# MCU.net
KiCad netlist of a schematic drawn in Altium Designer
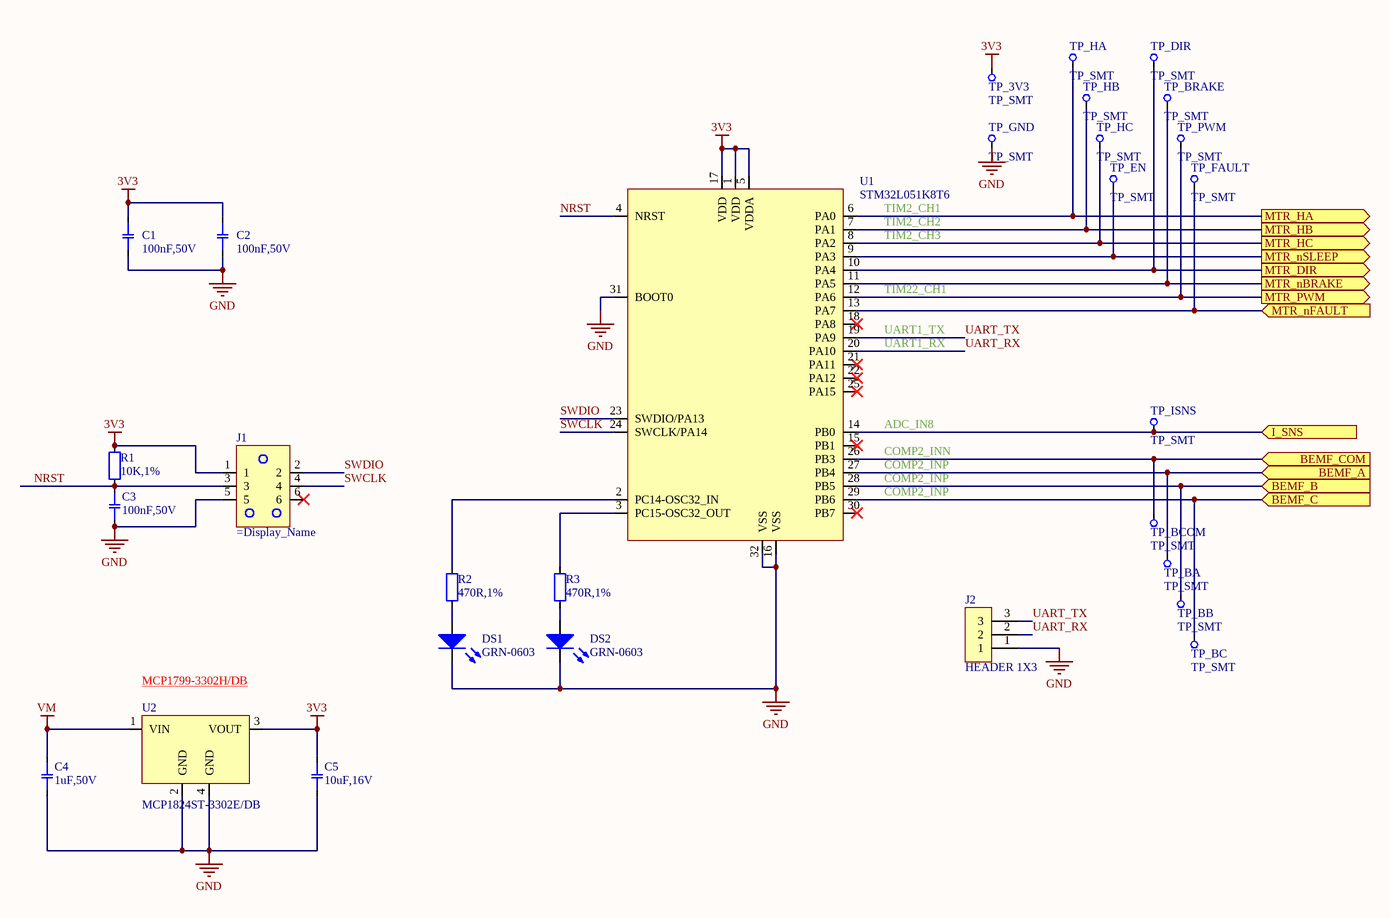
[diagram p0: MCU.SchDoc]

(export (version "E")
  (design (tool "Eeschema 10.0.6"))
  (components
    (comp (ref "C1")
      (value "100nF,50V")
      (footprint "CAPC1608X09N_0603")
      (description "CAP CER 0.1UF 50V 10% X7R 0603")
      (fields (field (name "MANUFACTURER") "Kemet") (field (name "TOLERANCE") "10%"))
      (libsource (lib "library") (part "CAP-NP_1"))
    )
    (comp (ref "C2")
      (value "100nF,50V")
      (footprint "CAPC1608X09N_0603")
      (description "CAP CER 0.1UF 50V 10% X7R 0603")
      (fields (field (name "MANUFACTURER") "Kemet") (field (name "TOLERANCE") "10%"))
      (libsource (lib "library") (part "CAP-NP_1"))
    )
    (comp (ref "C3")
      (value "100nF,50V")
      (footprint "CAPC1608X09N_0603")
      (description "CAP CER 0.1UF 50V 10% X7R 0603")
      (fields (field (name "MANUFACTURER") "Kemet") (field (name "TOLERANCE") "10%"))
      (libsource (lib "library") (part "CAP-NP_1"))
    )
    (comp (ref "C4")
      (value "1uF,50V")
      (footprint "CAPC1608X09N_0603")
      (description "AUTOMOTIVE CAP CER 1UF 50V 10% X5R 0603")
      (fields (field (name "MANUFACTURER") "TDK Corporation") (field (name "TOLERANCE") "10%"))
      (libsource (lib "library") (part "CAP-NP_1"))
    )
    (comp (ref "C5")
      (value "10uF,16V")
      (footprint "CAPC2012X12N_0805")
      (description "CAP CER 10µF ±10% 16V X7R 0805")
      (fields
        (field (name "MANUFACTURER") "Samsung Electro-Mechanics America, Inc.")
        (field (name "TOLERANCE") "10%")
      )
      (libsource (lib "library") (part "CAP-NP_1"))
    )
    (comp (ref "DS1")
      (value "GRN-0603")
      (footprint "LED_SML-LX0603")
      (description "LED GREEN CLEAR 0603 SMD")
      (fields
        (field (name "MANUFACTURER") "Dialight")
        (field (name "MANUFACTURER PART NUMBER") "5988081107F")
      )
      (libsource (lib "library") (part "LED_1"))
    )
    (comp (ref "DS2")
      (value "GRN-0603")
      (footprint "LED_SML-LX0603")
      (description "LED GREEN CLEAR 0603 SMD")
      (fields
        (field (name "MANUFACTURER") "Dialight")
        (field (name "MANUFACTURER PART NUMBER") "5988081107F")
      )
      (libsource (lib "library") (part "LED_1"))
    )
    (comp (ref "J1")
      (value "~")
      (footprint "TAG-CONNECT_TC2030-IDC")
      (description "Tag connect 6 way")
      (libsource (lib "library") (part "TAG-CONNECT_TC2030-IDC"))
    )
    (comp (ref "J2")
      (value "HEADER 1X3")
      (footprint "HIROSE_A2-3PA-2.54DSA")
      (description "CONN 3-pin 2.54mm pitch TH single row")
      (fields
        (field (name "MANUFACTURER") "Hirose")
        (field (name "MANUFACTURER PART NUMBER") "A2-3PA-2.54DSA")
      )
      (libsource (lib "library") (part "HIROSE_A2-3PA-2.54DSA"))
    )
    (comp (ref "R1")
      (value "10K,1%")
      (footprint "RESC1608X06N_0603")
      (description "RES 10.0K OHM 1/10W 1% 0603 SMD")
      (fields (field (name "MANUFACTURER") "Yageo") (field (name "POWER") "0.1W"))
      (libsource (lib "library") (part "RESISTOR_1"))
    )
    (comp (ref "R2")
      (value "470R,1%")
      (footprint "RESC1608X06N_0603")
      (description "RES 470 OHM 1/10W 1% 0603 SMD")
      (fields (field (name "MANUFACTURER") "Rohm Semiconductor") (field (name "POWER") "0.1W"))
      (libsource (lib "library") (part "RESISTOR_1"))
    )
    (comp (ref "R3")
      (value "470R,1%")
      (footprint "RESC1608X06N_0603")
      (description "RES 470 OHM 1/10W 1% 0603 SMD")
      (fields (field (name "MANUFACTURER") "Rohm Semiconductor") (field (name "POWER") "0.1W"))
      (libsource (lib "library") (part "RESISTOR_1"))
    )
    (comp (ref "TP_3V3")
      (value "TP_SMT")
      (footprint "TP_100X200")
      (description "Test Point - SMT")
      (libsource (lib "library") (part "TP_1"))
    )
    (comp (ref "TP_BA")
      (value "TP_SMT")
      (footprint "TP_100X200")
      (description "Test Point - SMT")
      (libsource (lib "library") (part "TP_1"))
    )
    (comp (ref "TP_BB")
      (value "TP_SMT")
      (footprint "TP_100X200")
      (description "Test Point - SMT")
      (libsource (lib "library") (part "TP_1"))
    )
    (comp (ref "TP_BC")
      (value "TP_SMT")
      (footprint "TP_100X200")
      (description "Test Point - SMT")
      (libsource (lib "library") (part "TP_1"))
    )
    (comp (ref "TP_BCOM")
      (value "TP_SMT")
      (footprint "TP_100X200")
      (description "Test Point - SMT")
      (libsource (lib "library") (part "TP_1"))
    )
    (comp (ref "TP_BRAKE")
      (value "TP_SMT")
      (footprint "TP_100X200")
      (description "Test Point - SMT")
      (libsource (lib "library") (part "TP_1"))
    )
    (comp (ref "TP_DIR")
      (value "TP_SMT")
      (footprint "TP_100X200")
      (description "Test Point - SMT")
      (libsource (lib "library") (part "TP_1"))
    )
    (comp (ref "TP_EN")
      (value "TP_SMT")
      (footprint "TP_100X200")
      (description "Test Point - SMT")
      (libsource (lib "library") (part "TP_1"))
    )
    (comp (ref "TP_FAULT")
      (value "TP_SMT")
      (footprint "TP_100X200")
      (description "Test Point - SMT")
      (libsource (lib "library") (part "TP_1"))
    )
    (comp (ref "TP_GND")
      (value "TP_SMT")
      (footprint "TP_100X200")
      (description "Test Point - SMT")
      (libsource (lib "library") (part "TP_1"))
    )
    (comp (ref "TP_HA")
      (value "TP_SMT")
      (footprint "TP_100X200")
      (description "Test Point - SMT")
      (libsource (lib "library") (part "TP_1"))
    )
    (comp (ref "TP_HB")
      (value "TP_SMT")
      (footprint "TP_100X200")
      (description "Test Point - SMT")
      (libsource (lib "library") (part "TP_1"))
    )
    (comp (ref "TP_HC")
      (value "TP_SMT")
      (footprint "TP_100X200")
      (description "Test Point - SMT")
      (libsource (lib "library") (part "TP_1"))
    )
    (comp (ref "TP_ISNS")
      (value "TP_SMT")
      (footprint "TP_100X200")
      (description "Test Point - SMT")
      (libsource (lib "library") (part "TP_1"))
    )
    (comp (ref "TP_PWM")
      (value "TP_SMT")
      (footprint "TP_100X200")
      (description "Test Point - SMT")
      (libsource (lib "library") (part "TP_1"))
    )
    (comp (ref "U1")
      (value "STM32L051K8T6")
      (footprint "LQFP32")
      (description "32 Bit Mcirocontroler")
      (fields (field (name "MANUFACTURER") "ST Microelectronics"))
      (libsource (lib "library") (part "STM32L051x6/8"))
    )
    (comp (ref "U2")
      (value "MCP1824ST-3302E/DB")
      (footprint "SOT230P700X180-4N_SOT223-3")
      (description "IC LDO REG 300MA 3.3V SOT223-3")
      (fields (field (name "MANUFACTURER") "Microchip Technology"))
      (libsource (lib "library") (part "MCP1824ST_DB"))
    )
  )
  (nets
    (net (code "1") (name "/BEMF_A") (class "Default")
      (node (ref "TP_BA") (pin "1") (pinfunction "1_1") (pintype "passive"))
      (node (ref "U1") (pin "27") (pinfunction "PB4_27") (pintype "passive"))
    )
    (net (code "2") (name "/BEMF_B") (class "Default")
      (node (ref "TP_BB") (pin "1") (pinfunction "1_1") (pintype "passive"))
      (node (ref "U1") (pin "28") (pinfunction "PB5_28") (pintype "passive"))
    )
    (net (code "3") (name "/BEMF_C") (class "Default")
      (node (ref "TP_BC") (pin "1") (pinfunction "1_1") (pintype "passive"))
      (node (ref "U1") (pin "29") (pinfunction "PB6_29") (pintype "passive"))
    )
    (net (code "4") (name "/BEMF_COM") (class "Default")
      (node (ref "TP_BCOM") (pin "1") (pinfunction "1_1") (pintype "passive"))
      (node (ref "U1") (pin "26") (pinfunction "PB3_26") (pintype "passive"))
    )
    (net (code "5") (name "/I_SNS") (class "Default")
      (node (ref "TP_ISNS") (pin "1") (pinfunction "1_1") (pintype "passive"))
      (node (ref "U1") (pin "14") (pinfunction "PB0_14") (pintype "passive"))
    )
    (net (code "6") (name "/MTR_DIR") (class "Default")
      (node (ref "TP_DIR") (pin "1") (pinfunction "1_1") (pintype "passive"))
      (node (ref "U1") (pin "10") (pinfunction "PA4_10") (pintype "passive"))
    )
    (net (code "7") (name "/MTR_HA") (class "Default")
      (node (ref "TP_HA") (pin "1") (pinfunction "1_1") (pintype "passive"))
      (node (ref "U1") (pin "6") (pinfunction "PA0_6") (pintype "passive"))
    )
    (net (code "8") (name "/MTR_HB") (class "Default")
      (node (ref "TP_HB") (pin "1") (pinfunction "1_1") (pintype "passive"))
      (node (ref "U1") (pin "7") (pinfunction "PA1_7") (pintype "passive"))
    )
    (net (code "9") (name "/MTR_HC") (class "Default")
      (node (ref "TP_HC") (pin "1") (pinfunction "1_1") (pintype "passive"))
      (node (ref "U1") (pin "8") (pinfunction "PA2_8") (pintype "passive"))
    )
    (net (code "10") (name "/MTR_PWM") (class "Default")
      (node (ref "TP_PWM") (pin "1") (pinfunction "1_1") (pintype "passive"))
      (node (ref "U1") (pin "12") (pinfunction "PA6_12") (pintype "passive"))
    )
    (net (code "11") (name "/MTR_nBRAKE") (class "Default")
      (node (ref "TP_BRAKE") (pin "1") (pinfunction "1_1") (pintype "passive"))
      (node (ref "U1") (pin "11") (pinfunction "PA5_11") (pintype "passive"))
    )
    (net (code "12") (name "/MTR_nFAULT") (class "Default")
      (node (ref "TP_FAULT") (pin "1") (pinfunction "1_1") (pintype "passive"))
      (node (ref "U1") (pin "13") (pinfunction "PA7_13") (pintype "passive"))
    )
    (net (code "13") (name "/MTR_nSLEEP") (class "Default")
      (node (ref "TP_EN") (pin "1") (pinfunction "1_1") (pintype "passive"))
      (node (ref "U1") (pin "9") (pinfunction "PA3_9") (pintype "passive"))
    )
    (net (code "14") (name "/NRST") (class "Default")
      (node (ref "C3") (pin "1") (pinfunction "1_1") (pintype "passive"))
      (node (ref "J1") (pin "3") (pinfunction "3_3") (pintype "passive"))
      (node (ref "R1") (pin "1") (pinfunction "1_1") (pintype "passive"))
      (node (ref "U1") (pin "4") (pinfunction "NRST_4") (pintype "passive"))
    )
    (net (code "15") (name "/SWCLK") (class "Default")
      (node (ref "J1") (pin "4") (pinfunction "4_4") (pintype "passive"))
      (node (ref "U1") (pin "24") (pinfunction "SWCLK/PA14_24") (pintype "passive"))
    )
    (net (code "16") (name "/SWDIO") (class "Default")
      (node (ref "J1") (pin "2") (pinfunction "2_2") (pintype "passive"))
      (node (ref "U1") (pin "23") (pinfunction "SWDIO/PA13_23") (pintype "passive"))
    )
    (net (code "17") (name "/UART_RX") (class "Default")
      (node (ref "J2") (pin "2") (pinfunction "2_2") (pintype "passive"))
      (node (ref "U1") (pin "20") (pinfunction "PA10_20") (pintype "passive"))
    )
    (net (code "18") (name "/UART_TX") (class "Default")
      (node (ref "J2") (pin "3") (pinfunction "3_3") (pintype "passive"))
      (node (ref "U1") (pin "19") (pinfunction "PA9_19") (pintype "passive"))
    )
    (net (code "19") (name "3V3") (class "Default")
      (node (ref "C1") (pin "2") (pinfunction "2_2") (pintype "passive"))
      (node (ref "C2") (pin "2") (pinfunction "2_2") (pintype "passive"))
      (node (ref "C5") (pin "2") (pinfunction "2_2") (pintype "passive"))
      (node (ref "J1") (pin "1") (pinfunction "1_1") (pintype "passive"))
      (node (ref "R1") (pin "2") (pinfunction "2_2") (pintype "passive"))
      (node (ref "TP_3V3") (pin "1") (pinfunction "1_1") (pintype "passive"))
      (node (ref "U1") (pin "1") (pinfunction "VDD_1") (pintype "passive"))
      (node (ref "U1") (pin "17") (pinfunction "VDD_17") (pintype "passive"))
      (node (ref "U1") (pin "5") (pinfunction "VDDA_5") (pintype "passive"))
      (node (ref "U2") (pin "3") (pinfunction "VOUT_3") (pintype "passive"))
    )
    (net (code "20") (name "GND") (class "Default")
      (node (ref "C1") (pin "1") (pinfunction "1_1") (pintype "passive"))
      (node (ref "C2") (pin "1") (pinfunction "1_1") (pintype "passive"))
      (node (ref "C3") (pin "2") (pinfunction "2_2") (pintype "passive"))
      (node (ref "C4") (pin "1") (pinfunction "1_1") (pintype "passive"))
      (node (ref "C5") (pin "1") (pinfunction "1_1") (pintype "passive"))
      (node (ref "DS1") (pin "1") (pinfunction "C_1") (pintype "passive"))
      (node (ref "DS2") (pin "1") (pinfunction "C_1") (pintype "passive"))
      (node (ref "J1") (pin "5") (pinfunction "5_5") (pintype "passive"))
      (node (ref "J2") (pin "1") (pinfunction "1_1") (pintype "passive"))
      (node (ref "TP_GND") (pin "1") (pinfunction "1_1") (pintype "passive"))
      (node (ref "U1") (pin "16") (pinfunction "VSS_16") (pintype "passive"))
      (node (ref "U1") (pin "31") (pinfunction "BOOT0_31") (pintype "passive"))
      (node (ref "U1") (pin "32") (pinfunction "VSS_32") (pintype "passive"))
      (node (ref "U2") (pin "2") (pinfunction "GND_2") (pintype "passive"))
      (node (ref "U2") (pin "4") (pinfunction "GND_4") (pintype "passive"))
    )
    (net (code "21") (name "Net-(DS1-A)") (class "Default")
      (node (ref "DS1") (pin "2") (pinfunction "A_2") (pintype "passive"))
      (node (ref "R2") (pin "1") (pinfunction "1_1") (pintype "passive"))
    )
    (net (code "22") (name "Net-(DS2-A)") (class "Default")
      (node (ref "DS2") (pin "2") (pinfunction "A_2") (pintype "passive"))
      (node (ref "R3") (pin "1") (pinfunction "1_1") (pintype "passive"))
    )
    (net (code "23") (name "Net-(U1-PC14-OSC32_IN)") (class "Default")
      (node (ref "R2") (pin "2") (pinfunction "2_2") (pintype "passive"))
      (node (ref "U1") (pin "2") (pinfunction "PC14-OSC32_IN_2") (pintype "passive"))
    )
    (net (code "24") (name "Net-(U1-PC15-OSC32_OUT)") (class "Default")
      (node (ref "R3") (pin "2") (pinfunction "2_2") (pintype "passive"))
      (node (ref "U1") (pin "3") (pinfunction "PC15-OSC32_OUT_3") (pintype "passive"))
    )
    (net (code "25") (name "VM") (class "Default")
      (node (ref "C4") (pin "2") (pinfunction "2_2") (pintype "passive"))
      (node (ref "U2") (pin "1") (pinfunction "VIN_1") (pintype "power_in"))
    )
    (net (code "26") (name "unconnected-(J1-Pad6)") (class "Default")
      (node (ref "J1") (pin "6") (pinfunction "6_6") (pintype "passive+no_connect"))
    )
    (net (code "27") (name "unconnected-(U1-PA8-Pad18)") (class "Default")
      (node (ref "U1") (pin "18") (pinfunction "PA8_18") (pintype "passive+no_connect"))
    )
    (net (code "28") (name "unconnected-(U1-PA11-Pad21)") (class "Default")
      (node (ref "U1") (pin "21") (pinfunction "PA11_21") (pintype "passive+no_connect"))
    )
    (net (code "29") (name "unconnected-(U1-PA12-Pad22)") (class "Default")
      (node (ref "U1") (pin "22") (pinfunction "PA12_22") (pintype "passive+no_connect"))
    )
    (net (code "30") (name "unconnected-(U1-PA15-Pad25)") (class "Default")
      (node (ref "U1") (pin "25") (pinfunction "PA15_25") (pintype "passive+no_connect"))
    )
    (net (code "31") (name "unconnected-(U1-PB1-Pad15)") (class "Default")
      (node (ref "U1") (pin "15") (pinfunction "PB1_15") (pintype "passive+no_connect"))
    )
    (net (code "32") (name "unconnected-(U1-PB7-Pad30)") (class "Default")
      (node (ref "U1") (pin "30") (pinfunction "PB7_30") (pintype "passive+no_connect"))
    )
  )
)
